# CONNECTORS.net
KiCad netlist of a schematic drawn in Altium Designer
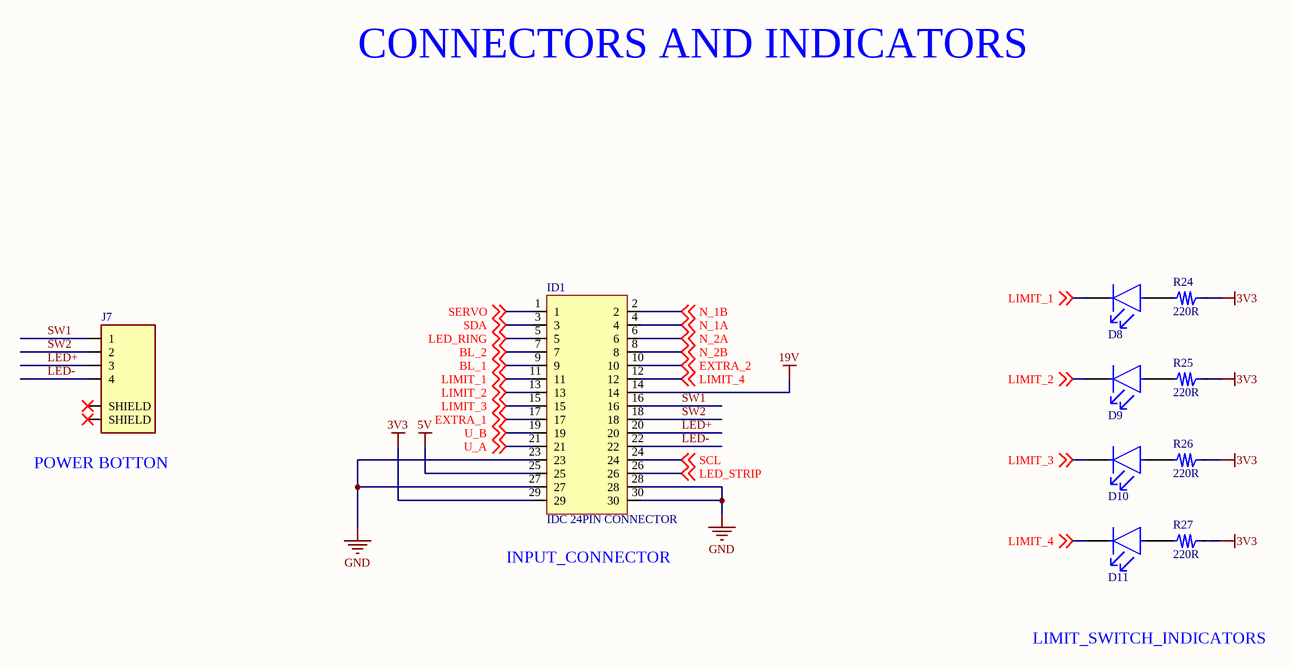
[diagram p0: CONNECTORS.SchDoc]

(export (version "E")
  (design (tool "Eeschema 10.0.6"))
  (components
    (comp (ref "D8")
      (value "LED")
      (footprint "LED")
      (fields (field (name "PART NUMBER") "XL-2012SURC"))
      (libsource (lib "Schlib2") (part "LED"))
    )
    (comp (ref "D9")
      (value "LED")
      (footprint "LED")
      (fields (field (name "PART NUMBER") "XL-2012SURC"))
      (libsource (lib "Schlib2") (part "LED"))
    )
    (comp (ref "D10")
      (value "LED")
      (footprint "LED")
      (fields (field (name "PART NUMBER") "XL-2012SURC"))
      (libsource (lib "Schlib2") (part "LED"))
    )
    (comp (ref "D11")
      (value "LED")
      (footprint "LED")
      (fields (field (name "PART NUMBER") "XL-2012SURC"))
      (libsource (lib "Schlib2") (part "LED"))
    )
    (comp (ref "ID1")
      (value "IDC 24PIN CONNECTOR")
      (footprint "IDC 30 PIN")
      (fields (field (name "PART NUMBER") "ZX-IDC2.54-2-15PZZ"))
      (libsource (lib "Schlib2") (part "IDC 24PIN CONNECTOR"))
    )
    (comp (ref "J7")
      (value "SM04B-SRSS-TB(LF)(SN)")
      (footprint "JST_SM04B-SRSS-TB(LF)(SN)")
      (description "Connector Header Surface Mount, Right Angle 4 position 0.039 (1.00mm)")
      (libsource (lib "Schlib2") (part "SM04B-SRSS-TB(LF)(SN)"))
    )
    (comp (ref "R24")
      (value "220R")
      (footprint "RES 0603")
      (fields (field (name "PART NUMBER") "RC0603JR-07220RL"))
      (libsource (lib "Schlib2") (part "Resistor"))
    )
    (comp (ref "R25")
      (value "220R")
      (footprint "RES 0603")
      (fields (field (name "PART NUMBER") "RC0603JR-07220RL"))
      (libsource (lib "Schlib2") (part "Resistor"))
    )
    (comp (ref "R26")
      (value "220R")
      (footprint "RES 0603")
      (fields (field (name "PART NUMBER") "RC0603JR-07220RL"))
      (libsource (lib "Schlib2") (part "Resistor"))
    )
    (comp (ref "R27")
      (value "220R")
      (footprint "RES 0603")
      (fields (field (name "PART NUMBER") "RC0603JR-07220RL"))
      (libsource (lib "Schlib2") (part "Resistor"))
    )
  )
  (nets
    (net (code "1") (name "/LED+") (class "Default")
      (node (ref "ID1") (pin "20") (pinfunction "20_20") (pintype "passive"))
      (node (ref "J7") (pin "3") (pinfunction "3_3") (pintype "passive"))
    )
    (net (code "2") (name "/LED-") (class "Default")
      (node (ref "ID1") (pin "22") (pinfunction "22_22") (pintype "passive"))
      (node (ref "J7") (pin "4") (pinfunction "4_4") (pintype "passive"))
    )
    (net (code "3") (name "/SW1") (class "Default")
      (node (ref "ID1") (pin "16") (pinfunction "16_16") (pintype "passive"))
      (node (ref "J7") (pin "1") (pinfunction "1_1") (pintype "passive"))
    )
    (net (code "4") (name "/SW2") (class "Default")
      (node (ref "ID1") (pin "18") (pinfunction "18_18") (pintype "passive"))
      (node (ref "J7") (pin "2") (pinfunction "2_2") (pintype "passive"))
    )
    (net (code "5") (name "3V3") (class "Default")
      (node (ref "ID1") (pin "29") (pinfunction "29_29") (pintype "passive"))
      (node (ref "R24") (pin "1") (pinfunction "1_1") (pintype "passive"))
      (node (ref "R25") (pin "1") (pinfunction "1_1") (pintype "passive"))
      (node (ref "R26") (pin "1") (pinfunction "1_1") (pintype "passive"))
      (node (ref "R27") (pin "1") (pinfunction "1_1") (pintype "passive"))
    )
    (net (code "6") (name "5V") (class "Default")
      (node (ref "ID1") (pin "25") (pinfunction "25_25") (pintype "passive"))
    )
    (net (code "7") (name "19V") (class "Default")
      (node (ref "ID1") (pin "14") (pinfunction "14_14") (pintype "passive"))
    )
    (net (code "8") (name "BL_1") (class "Default")
      (node (ref "ID1") (pin "9") (pinfunction "9_9") (pintype "passive"))
    )
    (net (code "9") (name "BL_2") (class "Default")
      (node (ref "ID1") (pin "7") (pinfunction "7_7") (pintype "passive"))
    )
    (net (code "10") (name "EXTRA_1") (class "Default")
      (node (ref "ID1") (pin "17") (pinfunction "17_17") (pintype "passive"))
    )
    (net (code "11") (name "EXTRA_2") (class "Default")
      (node (ref "ID1") (pin "10") (pinfunction "10_10") (pintype "passive"))
    )
    (net (code "12") (name "GND") (class "Default")
      (node (ref "ID1") (pin "23") (pinfunction "23_23") (pintype "passive"))
      (node (ref "ID1") (pin "27") (pinfunction "27_27") (pintype "passive"))
      (node (ref "ID1") (pin "28") (pinfunction "28_28") (pintype "passive"))
      (node (ref "ID1") (pin "30") (pinfunction "30_30") (pintype "passive"))
    )
    (net (code "13") (name "LED_RING") (class "Default")
      (node (ref "ID1") (pin "5") (pinfunction "5_5") (pintype "passive"))
    )
    (net (code "14") (name "LED_STRIP") (class "Default")
      (node (ref "ID1") (pin "26") (pinfunction "26_26") (pintype "passive"))
    )
    (net (code "15") (name "LIMIT_1") (class "Default")
      (node (ref "D8") (pin "1") (pinfunction "C_1") (pintype "passive"))
      (node (ref "ID1") (pin "11") (pinfunction "11_11") (pintype "passive"))
    )
    (net (code "16") (name "LIMIT_2") (class "Default")
      (node (ref "D9") (pin "1") (pinfunction "C_1") (pintype "passive"))
      (node (ref "ID1") (pin "13") (pinfunction "13_13") (pintype "passive"))
    )
    (net (code "17") (name "LIMIT_3") (class "Default")
      (node (ref "D10") (pin "1") (pinfunction "C_1") (pintype "passive"))
      (node (ref "ID1") (pin "15") (pinfunction "15_15") (pintype "passive"))
    )
    (net (code "18") (name "LIMIT_4") (class "Default")
      (node (ref "D11") (pin "1") (pinfunction "C_1") (pintype "passive"))
      (node (ref "ID1") (pin "12") (pinfunction "12_12") (pintype "passive"))
    )
    (net (code "19") (name "N_1A") (class "Default")
      (node (ref "ID1") (pin "4") (pinfunction "4_4") (pintype "passive"))
    )
    (net (code "20") (name "N_1B") (class "Default")
      (node (ref "ID1") (pin "2") (pinfunction "2_2") (pintype "passive"))
    )
    (net (code "21") (name "N_2A") (class "Default")
      (node (ref "ID1") (pin "6") (pinfunction "6_6") (pintype "passive"))
    )
    (net (code "22") (name "N_2B") (class "Default")
      (node (ref "ID1") (pin "8") (pinfunction "8_8") (pintype "passive"))
    )
    (net (code "23") (name "Net-(D8-A)") (class "Default")
      (node (ref "D8") (pin "2") (pinfunction "A_2") (pintype "passive"))
      (node (ref "R24") (pin "2") (pinfunction "2_2") (pintype "passive"))
    )
    (net (code "24") (name "Net-(D9-A)") (class "Default")
      (node (ref "D9") (pin "2") (pinfunction "A_2") (pintype "passive"))
      (node (ref "R25") (pin "2") (pinfunction "2_2") (pintype "passive"))
    )
    (net (code "25") (name "Net-(D10-A)") (class "Default")
      (node (ref "D10") (pin "2") (pinfunction "A_2") (pintype "passive"))
      (node (ref "R26") (pin "2") (pinfunction "2_2") (pintype "passive"))
    )
    (net (code "26") (name "Net-(D11-A)") (class "Default")
      (node (ref "D11") (pin "2") (pinfunction "A_2") (pintype "passive"))
      (node (ref "R27") (pin "2") (pinfunction "2_2") (pintype "passive"))
    )
    (net (code "27") (name "SCL") (class "Default")
      (node (ref "ID1") (pin "24") (pinfunction "24_24") (pintype "passive"))
    )
    (net (code "28") (name "SDA") (class "Default")
      (node (ref "ID1") (pin "3") (pinfunction "3_3") (pintype "passive"))
    )
    (net (code "29") (name "SERVO") (class "Default")
      (node (ref "ID1") (pin "1") (pinfunction "1_1") (pintype "passive"))
    )
    (net (code "30") (name "U_A") (class "Default")
      (node (ref "ID1") (pin "21") (pinfunction "21_21") (pintype "passive"))
    )
    (net (code "31") (name "U_B") (class "Default")
      (node (ref "ID1") (pin "19") (pinfunction "19_19") (pintype "passive"))
    )
    (net (code "32") (name "unconnected-(J7-SHIELD-PadS1)") (class "Default")
      (node (ref "J7") (pin "S1") (pinfunction "SHIELD_S1") (pintype "passive+no_connect"))
    )
    (net (code "33") (name "unconnected-(J7-SHIELD-PadS2)") (class "Default")
      (node (ref "J7") (pin "S2") (pinfunction "SHIELD_S2") (pintype "passive+no_connect"))
    )
  )
)
